# Sheet1.net
KiCad netlist of a schematic drawn in Altium Designer
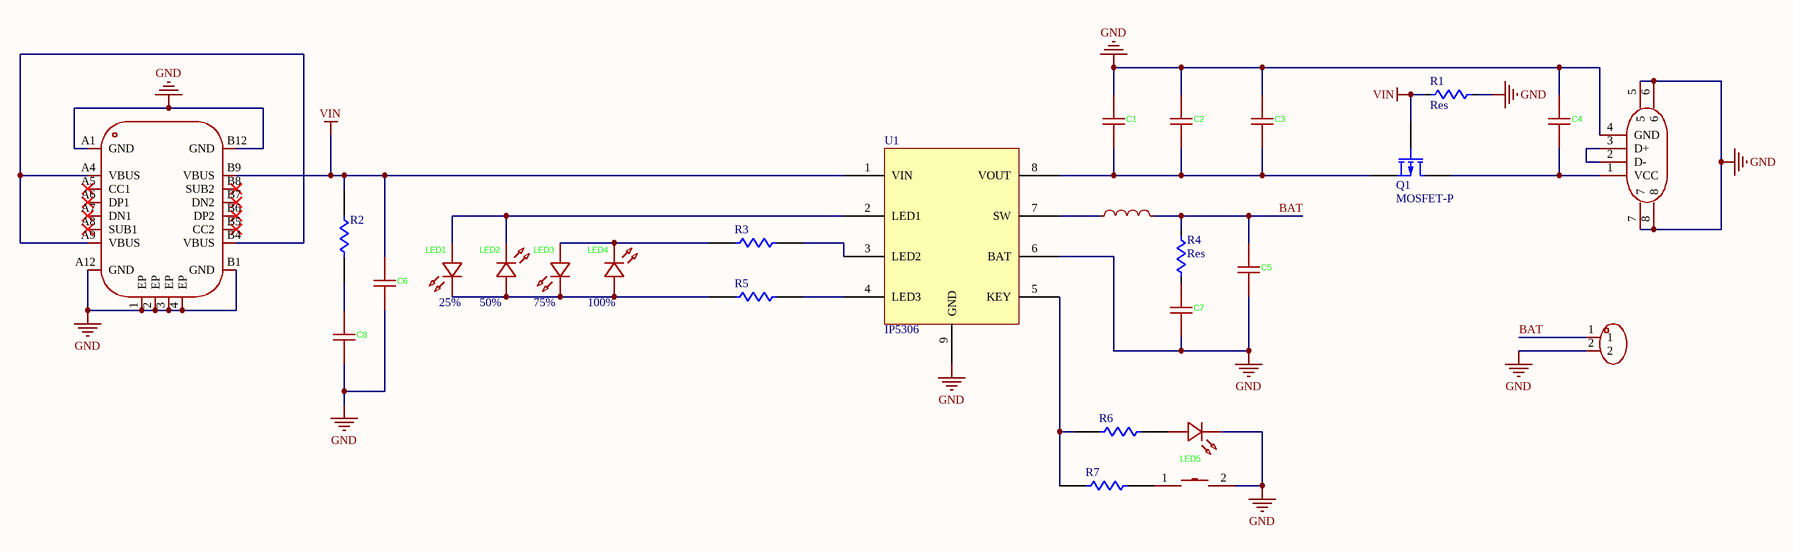
[diagram p0: Sheet1.SchDoc]

(export (version "E")
  (design (tool "Eeschema 10.0.6"))
  (components
    (comp (ref "C1")
      (value "Capacitor_Patch")
      (footprint "C0805")
      (description "0805")
      (fields
        (field (name "MANUFACTURER") "SAMSUNG(三星)")
        (field (name "MANUFACTURER PART") "CL21A106KAYNNNE")
      )
      (libsource (lib "PCB_Project") (part "Capacitor_Patch"))
    )
    (comp (ref "C2")
      (value "Capacitor_Patch")
      (footprint "C0805")
      (description "0805")
      (fields
        (field (name "MANUFACTURER") "SAMSUNG(三星)")
        (field (name "MANUFACTURER PART") "CL21A106KAYNNNE")
      )
      (libsource (lib "PCB_Project") (part "Capacitor_Patch"))
    )
    (comp (ref "C3")
      (value "Capacitor_Patch")
      (footprint "C0805")
      (description "0805")
      (fields
        (field (name "MANUFACTURER") "SAMSUNG(三星)")
        (field (name "MANUFACTURER PART") "CL21A106KAYNNNE")
      )
      (libsource (lib "PCB_Project") (part "Capacitor_Patch"))
    )
    (comp (ref "C4")
      (value "Capacitor_Patch")
      (footprint "C0805")
      (description "0805")
      (fields
        (field (name "MANUFACTURER") "SAMSUNG(三星)")
        (field (name "MANUFACTURER PART") "CL21A106KAYNNNE")
      )
      (libsource (lib "PCB_Project") (part "Capacitor_Patch"))
    )
    (comp (ref "C5")
      (value "Capacitor_Patch")
      (footprint "C0805")
      (description "0805")
      (fields
        (field (name "MANUFACTURER") "SAMSUNG(三星)")
        (field (name "MANUFACTURER PART") "CL21A106KAYNNNE")
      )
      (libsource (lib "PCB_Project") (part "Capacitor_Patch"))
    )
    (comp (ref "C6")
      (value "Capacitor_Patch")
      (footprint "C0805")
      (description "0805")
      (fields
        (field (name "MANUFACTURER") "SAMSUNG(三星)")
        (field (name "MANUFACTURER PART") "CL21A106KAYNNNE")
      )
      (libsource (lib "PCB_Project") (part "Capacitor_Patch"))
    )
    (comp (ref "C7")
      (value "Capacitor_Patch")
      (footprint "C0805")
      (description "0805")
      (fields
        (field (name "MANUFACTURER") "SAMSUNG(三星)")
        (field (name "MANUFACTURER PART") "CL21A106KAYNNNE")
      )
      (libsource (lib "PCB_Project") (part "Capacitor_Patch"))
    )
    (comp (ref "C8")
      (value "Capacitor_Patch")
      (footprint "C0805")
      (description "0805")
      (fields
        (field (name "MANUFACTURER") "SAMSUNG(三星)")
        (field (name "MANUFACTURER PART") "CL21A106KAYNNNE")
      )
      (libsource (lib "PCB_Project") (part "Capacitor_Patch"))
    )
    (comp (ref "CN1")
      (value "HX25003-2WAP")
      (footprint "CONN-TH_2P-P2.50_HX25003-2WAP")
      (fields (field (name "MANUFACTURER") "HX(红星)"))
      (libsource (lib "PCB_Project") (part "HX25003-2WAP"))
    )
    (comp (ref "LED1")
      (value "LED_Patch")
      (footprint "PCBComponent_1")
      (description "0805")
      (fields (field (name "MANUFACTURER") "XINGLIGHT(成兴光)") (field (name "MANUFACTURER PART") "XL-2012UGC"))
      (libsource (lib "PCB_Project") (part "LED_Patch"))
    )
    (comp (ref "LED2")
      (value "LED_Patch")
      (footprint "PCBComponent_1")
      (description "0805")
      (fields (field (name "MANUFACTURER") "XINGLIGHT(成兴光)") (field (name "MANUFACTURER PART") "XL-2012UGC"))
      (libsource (lib "PCB_Project") (part "LED_Patch"))
    )
    (comp (ref "LED3")
      (value "LED_Patch")
      (footprint "PCBComponent_1")
      (description "0805")
      (fields (field (name "MANUFACTURER") "XINGLIGHT(成兴光)") (field (name "MANUFACTURER PART") "XL-2012UGC"))
      (libsource (lib "PCB_Project") (part "LED_Patch"))
    )
    (comp (ref "LED4")
      (value "LED_Patch")
      (footprint "PCBComponent_1")
      (description "0805")
      (fields (field (name "MANUFACTURER") "XINGLIGHT(成兴光)") (field (name "MANUFACTURER PART") "XL-2012UGC"))
      (libsource (lib "PCB_Project") (part "LED_Patch"))
    )
    (comp (ref "LED5")
      (value "LED_Patch")
      (footprint "PCBComponent_1")
      (description "0805")
      (fields (field (name "MANUFACTURER") "XINGLIGHT(成兴光)") (field (name "MANUFACTURER PART") "XL-2012UGC"))
      (libsource (lib "PCB_Project") (part "LED_Patch"))
    )
    (comp (ref "Q1")
      (value "MOSFET-P")
      (footprint "SOT23_M")
      (description "P-Channel MOSFET")
      (fields (field (name "PUBLISHER") "Altium Limited"))
      (libsource (lib "Miscellaneous Devices") (part "MOSFET-P"))
    )
    (comp (ref "R1")
      (value "Res")
      (footprint "6-0805_N")
      (fields (field (name "PUBLISHER") "Altium Limited"))
      (libsource (lib "") (part "Res_1"))
    )
    (comp (ref "R2")
      (value "Res")
      (footprint "6-0805_N")
      (fields (field (name "PUBLISHER") "Altium Limited"))
      (libsource (lib "PCB_Project") (part "Res"))
    )
    (comp (ref "R3")
      (value "Res")
      (footprint "6-0805_N")
      (fields (field (name "PUBLISHER") "Altium Limited"))
      (libsource (lib "PCB_Project") (part "Res"))
    )
    (comp (ref "R4")
      (value "Res")
      (footprint "6-0805_N")
      (fields (field (name "PUBLISHER") "Altium Limited"))
      (libsource (lib "") (part "Res_1"))
    )
    (comp (ref "R5")
      (value "Res")
      (footprint "6-0805_N")
      (fields (field (name "PUBLISHER") "Altium Limited"))
      (libsource (lib "PCB_Project") (part "Res"))
    )
    (comp (ref "R6")
      (value "Res")
      (footprint "6-0805_N")
      (fields (field (name "PUBLISHER") "Altium Limited"))
      (libsource (lib "PCB_Project") (part "Res"))
    )
    (comp (ref "R7")
      (value "Res")
      (footprint "6-0805_N")
      (fields (field (name "PUBLISHER") "Altium Limited"))
      (libsource (lib "PCB_Project") (part "Res"))
    )
    (comp (ref "SW1")
      (value "TS-1101-C-W")
      (footprint "SW-SMD_L6.0-W3.3-LS8.0")
      (fields (field (name "MANUFACTURER") "XKB Connectivity(中国星坤)"))
      (libsource (lib "PCB_Project") (part "TS-1101-C-W"))
    )
    (comp (ref "U1")
      (value "IP5306")
      (footprint "ESOP-8_L4.9-W3.9-P1.27-LS6.0-BL-EP")
      (description "IC")
      (libsource (lib "PCB_Project") (part "IP5306"))
    )
    (comp (ref "U2")
      (value "1uH")
      (footprint "IND-SMD_L4.4-W4.2")
      (fields
        (field (name "MANUFACTURER") "XR(祥如)")
        (field (name "MANUFACTURER PART") "XR0420-1R0M")
        (field (name "TOLERANCE") "±20%")
      )
      (libsource (lib "PCB_Project") (part "Inductor_SMD"))
    )
    (comp (ref "USB1")
      (value "10.0 QTJ6.3")
      (footprint "USB-A-SMD_10.0-QTJ6.3")
      (fields (field (name "MANUFACTURER") "SHOU HAN(首韩)"))
      (libsource (lib "PCB_Project") (part "10.0 QTJ6.3"))
    )
    (comp (ref "USB2")
      (value "KH-TYPE-C-16P")
      (footprint "USB-C-SMD_KH-TYPE-C-16P")
      (fields (field (name "MANUFACTURER") "kinghelm(金航标)"))
      (libsource (lib "Schlib1") (part "KH-TYPE-C-16P"))
    )
  )
  (nets
    (net (code "1") (name "/BAT") (class "Default")
      (node (ref "C5") (pin "2") (pinfunction "2_2") (pintype "passive"))
      (node (ref "CN1") (pin "1") (pinfunction "1_1") (pintype "passive"))
      (node (ref "R4") (pin "1") (pinfunction "1_1") (pintype "passive"))
      (node (ref "U2") (pin "2") (pinfunction "2_2") (pintype "passive"))
    )
    (net (code "2") (name "GND") (class "Default")
      (node (ref "C1") (pin "2") (pinfunction "2_2") (pintype "passive"))
      (node (ref "C2") (pin "2") (pinfunction "2_2") (pintype "passive"))
      (node (ref "C3") (pin "2") (pinfunction "2_2") (pintype "passive"))
      (node (ref "C4") (pin "2") (pinfunction "2_2") (pintype "passive"))
      (node (ref "C5") (pin "1") (pinfunction "1_1") (pintype "passive"))
      (node (ref "C6") (pin "1") (pinfunction "1_1") (pintype "passive"))
      (node (ref "C7") (pin "1") (pinfunction "1_1") (pintype "passive"))
      (node (ref "C8") (pin "1") (pinfunction "1_1") (pintype "passive"))
      (node (ref "CN1") (pin "2") (pinfunction "2_2") (pintype "passive"))
      (node (ref "LED5") (pin "1") (pinfunction "K_1") (pintype "passive"))
      (node (ref "R1") (pin "1") (pinfunction "1_1") (pintype "passive"))
      (node (ref "SW1") (pin "2") (pinfunction "2_2") (pintype "passive"))
      (node (ref "U1") (pin "6") (pinfunction "BAT_6") (pintype "passive"))
      (node (ref "U1") (pin "9") (pinfunction "GND_9") (pintype "passive"))
      (node (ref "USB1") (pin "4") (pinfunction "GND_4") (pintype "passive"))
      (node (ref "USB1") (pin "5") (pinfunction "5_5") (pintype "passive"))
      (node (ref "USB1") (pin "6") (pinfunction "6_6") (pintype "passive"))
      (node (ref "USB1") (pin "7") (pinfunction "7_7") (pintype "passive"))
      (node (ref "USB1") (pin "8") (pinfunction "8_8") (pintype "passive"))
      (node (ref "USB2") (pin "1") (pinfunction "EP_1") (pintype "passive"))
      (node (ref "USB2") (pin "2") (pinfunction "EP_2") (pintype "passive"))
      (node (ref "USB2") (pin "3") (pinfunction "EP_3") (pintype "passive"))
      (node (ref "USB2") (pin "4") (pinfunction "EP_4") (pintype "passive"))
      (node (ref "USB2") (pin "A1") (pinfunction "GND_A1") (pintype "passive"))
      (node (ref "USB2") (pin "A12") (pinfunction "GND_A12") (pintype "passive"))
      (node (ref "USB2") (pin "B1") (pinfunction "GND_B1") (pintype "passive"))
      (node (ref "USB2") (pin "B12") (pinfunction "GND_B12") (pintype "passive"))
    )
    (net (code "3") (name "Net-(C7-Pad2)") (class "Default")
      (node (ref "C7") (pin "2") (pinfunction "2_2") (pintype "passive"))
      (node (ref "R4") (pin "2") (pinfunction "2_2") (pintype "passive"))
    )
    (net (code "4") (name "Net-(C8-Pad2)") (class "Default")
      (node (ref "C8") (pin "2") (pinfunction "2_2") (pintype "passive"))
      (node (ref "R2") (pin "2") (pinfunction "2_2") (pintype "passive"))
    )
    (net (code "5") (name "Net-(LED1-A)") (class "Default")
      (node (ref "LED1") (pin "2") (pinfunction "A_2") (pintype "passive"))
      (node (ref "LED2") (pin "1") (pinfunction "K_1") (pintype "passive"))
      (node (ref "U1") (pin "2") (pinfunction "LED1_2") (pintype "passive"))
    )
    (net (code "6") (name "Net-(LED1-K)") (class "Default")
      (node (ref "LED1") (pin "1") (pinfunction "K_1") (pintype "passive"))
      (node (ref "LED2") (pin "2") (pinfunction "A_2") (pintype "passive"))
      (node (ref "LED3") (pin "1") (pinfunction "K_1") (pintype "passive"))
      (node (ref "LED4") (pin "2") (pinfunction "A_2") (pintype "passive"))
      (node (ref "R5") (pin "1") (pinfunction "1_1") (pintype "passive"))
    )
    (net (code "7") (name "Net-(LED3-A)") (class "Default")
      (node (ref "LED3") (pin "2") (pinfunction "A_2") (pintype "passive"))
      (node (ref "LED4") (pin "1") (pinfunction "K_1") (pintype "passive"))
      (node (ref "R3") (pin "1") (pinfunction "1_1") (pintype "passive"))
    )
    (net (code "8") (name "Net-(LED5-A)") (class "Default")
      (node (ref "LED5") (pin "2") (pinfunction "A_2") (pintype "passive"))
      (node (ref "R6") (pin "2") (pinfunction "2_2") (pintype "passive"))
    )
    (net (code "9") (name "Net-(Q1-D)") (class "Default")
      (node (ref "C4") (pin "1") (pinfunction "1_1") (pintype "passive"))
      (node (ref "Q1") (pin "1") (pinfunction "D_1") (pintype "passive"))
      (node (ref "USB1") (pin "1") (pinfunction "VCC_1") (pintype "passive"))
    )
    (net (code "10") (name "Net-(Q1-S)") (class "Default")
      (node (ref "C1") (pin "1") (pinfunction "1_1") (pintype "passive"))
      (node (ref "C2") (pin "1") (pinfunction "1_1") (pintype "passive"))
      (node (ref "C3") (pin "1") (pinfunction "1_1") (pintype "passive"))
      (node (ref "Q1") (pin "3") (pinfunction "S_3") (pintype "passive"))
      (node (ref "U1") (pin "8") (pinfunction "VOUT_8") (pintype "passive"))
    )
    (net (code "11") (name "Net-(R7-Pad2)") (class "Default")
      (node (ref "R7") (pin "2") (pinfunction "2_2") (pintype "passive"))
      (node (ref "SW1") (pin "1") (pinfunction "1_1") (pintype "passive"))
    )
    (net (code "12") (name "Net-(U1-KEY)") (class "Default")
      (node (ref "R6") (pin "1") (pinfunction "1_1") (pintype "passive"))
      (node (ref "R7") (pin "1") (pinfunction "1_1") (pintype "passive"))
      (node (ref "U1") (pin "5") (pinfunction "KEY_5") (pintype "passive"))
    )
    (net (code "13") (name "Net-(U1-LED2)") (class "Default")
      (node (ref "R3") (pin "2") (pinfunction "2_2") (pintype "passive"))
      (node (ref "U1") (pin "3") (pinfunction "LED2_3") (pintype "passive"))
    )
    (net (code "14") (name "Net-(U1-LED3)") (class "Default")
      (node (ref "R5") (pin "2") (pinfunction "2_2") (pintype "passive"))
      (node (ref "U1") (pin "4") (pinfunction "LED3_4") (pintype "passive"))
    )
    (net (code "15") (name "Net-(U1-SW)") (class "Default")
      (node (ref "U1") (pin "7") (pinfunction "SW_7") (pintype "passive"))
      (node (ref "U2") (pin "1") (pinfunction "1_1") (pintype "passive"))
    )
    (net (code "16") (name "Net-(USB1-D+)") (class "Default")
      (node (ref "USB1") (pin "2") (pinfunction "D-_2") (pintype "passive"))
      (node (ref "USB1") (pin "3") (pinfunction "D+_3") (pintype "passive"))
    )
    (net (code "17") (name "Net-(USB2-VBUS-PadA4)") (class "Default")
      (node (ref "USB2") (pin "A4") (pinfunction "VBUS_A4") (pintype "passive"))
      (node (ref "USB2") (pin "A9") (pinfunction "VBUS_A9") (pintype "passive"))
      (node (ref "USB2") (pin "B4") (pinfunction "VBUS_B4") (pintype "passive"))
    )
    (net (code "18") (name "VIN") (class "Default")
      (node (ref "C6") (pin "2") (pinfunction "2_2") (pintype "passive"))
      (node (ref "Q1") (pin "2") (pinfunction "G_2") (pintype "passive"))
      (node (ref "R1") (pin "2") (pinfunction "2_2") (pintype "passive"))
      (node (ref "R2") (pin "1") (pinfunction "1_1") (pintype "passive"))
      (node (ref "U1") (pin "1") (pinfunction "VIN_1") (pintype "passive"))
      (node (ref "USB2") (pin "B9") (pinfunction "VBUS_B9") (pintype "passive"))
    )
    (net (code "19") (name "unconnected-(USB2-CC1-PadA5)") (class "Default")
      (node (ref "USB2") (pin "A5") (pinfunction "CC1_A5") (pintype "passive+no_connect"))
    )
    (net (code "20") (name "unconnected-(USB2-CC2-PadB5)") (class "Default")
      (node (ref "USB2") (pin "B5") (pinfunction "CC2_B5") (pintype "passive+no_connect"))
    )
    (net (code "21") (name "unconnected-(USB2-DN1-PadA7)") (class "Default")
      (node (ref "USB2") (pin "A7") (pinfunction "DN1_A7") (pintype "passive+no_connect"))
    )
    (net (code "22") (name "unconnected-(USB2-DN2-PadB7)") (class "Default")
      (node (ref "USB2") (pin "B7") (pinfunction "DN2_B7") (pintype "passive+no_connect"))
    )
    (net (code "23") (name "unconnected-(USB2-DP1-PadA6)") (class "Default")
      (node (ref "USB2") (pin "A6") (pinfunction "DP1_A6") (pintype "passive+no_connect"))
    )
    (net (code "24") (name "unconnected-(USB2-DP2-PadB6)") (class "Default")
      (node (ref "USB2") (pin "B6") (pinfunction "DP2_B6") (pintype "passive+no_connect"))
    )
    (net (code "25") (name "unconnected-(USB2-SUB1-PadA8)") (class "Default")
      (node (ref "USB2") (pin "A8") (pinfunction "SUB1_A8") (pintype "passive+no_connect"))
    )
    (net (code "26") (name "unconnected-(USB2-SUB2-PadB8)") (class "Default")
      (node (ref "USB2") (pin "B8") (pinfunction "SUB2_B8") (pintype "passive+no_connect"))
    )
  )
)
